# P13_ETH1_RGMII.net
KiCad netlist of a schematic drawn in Altium Designer
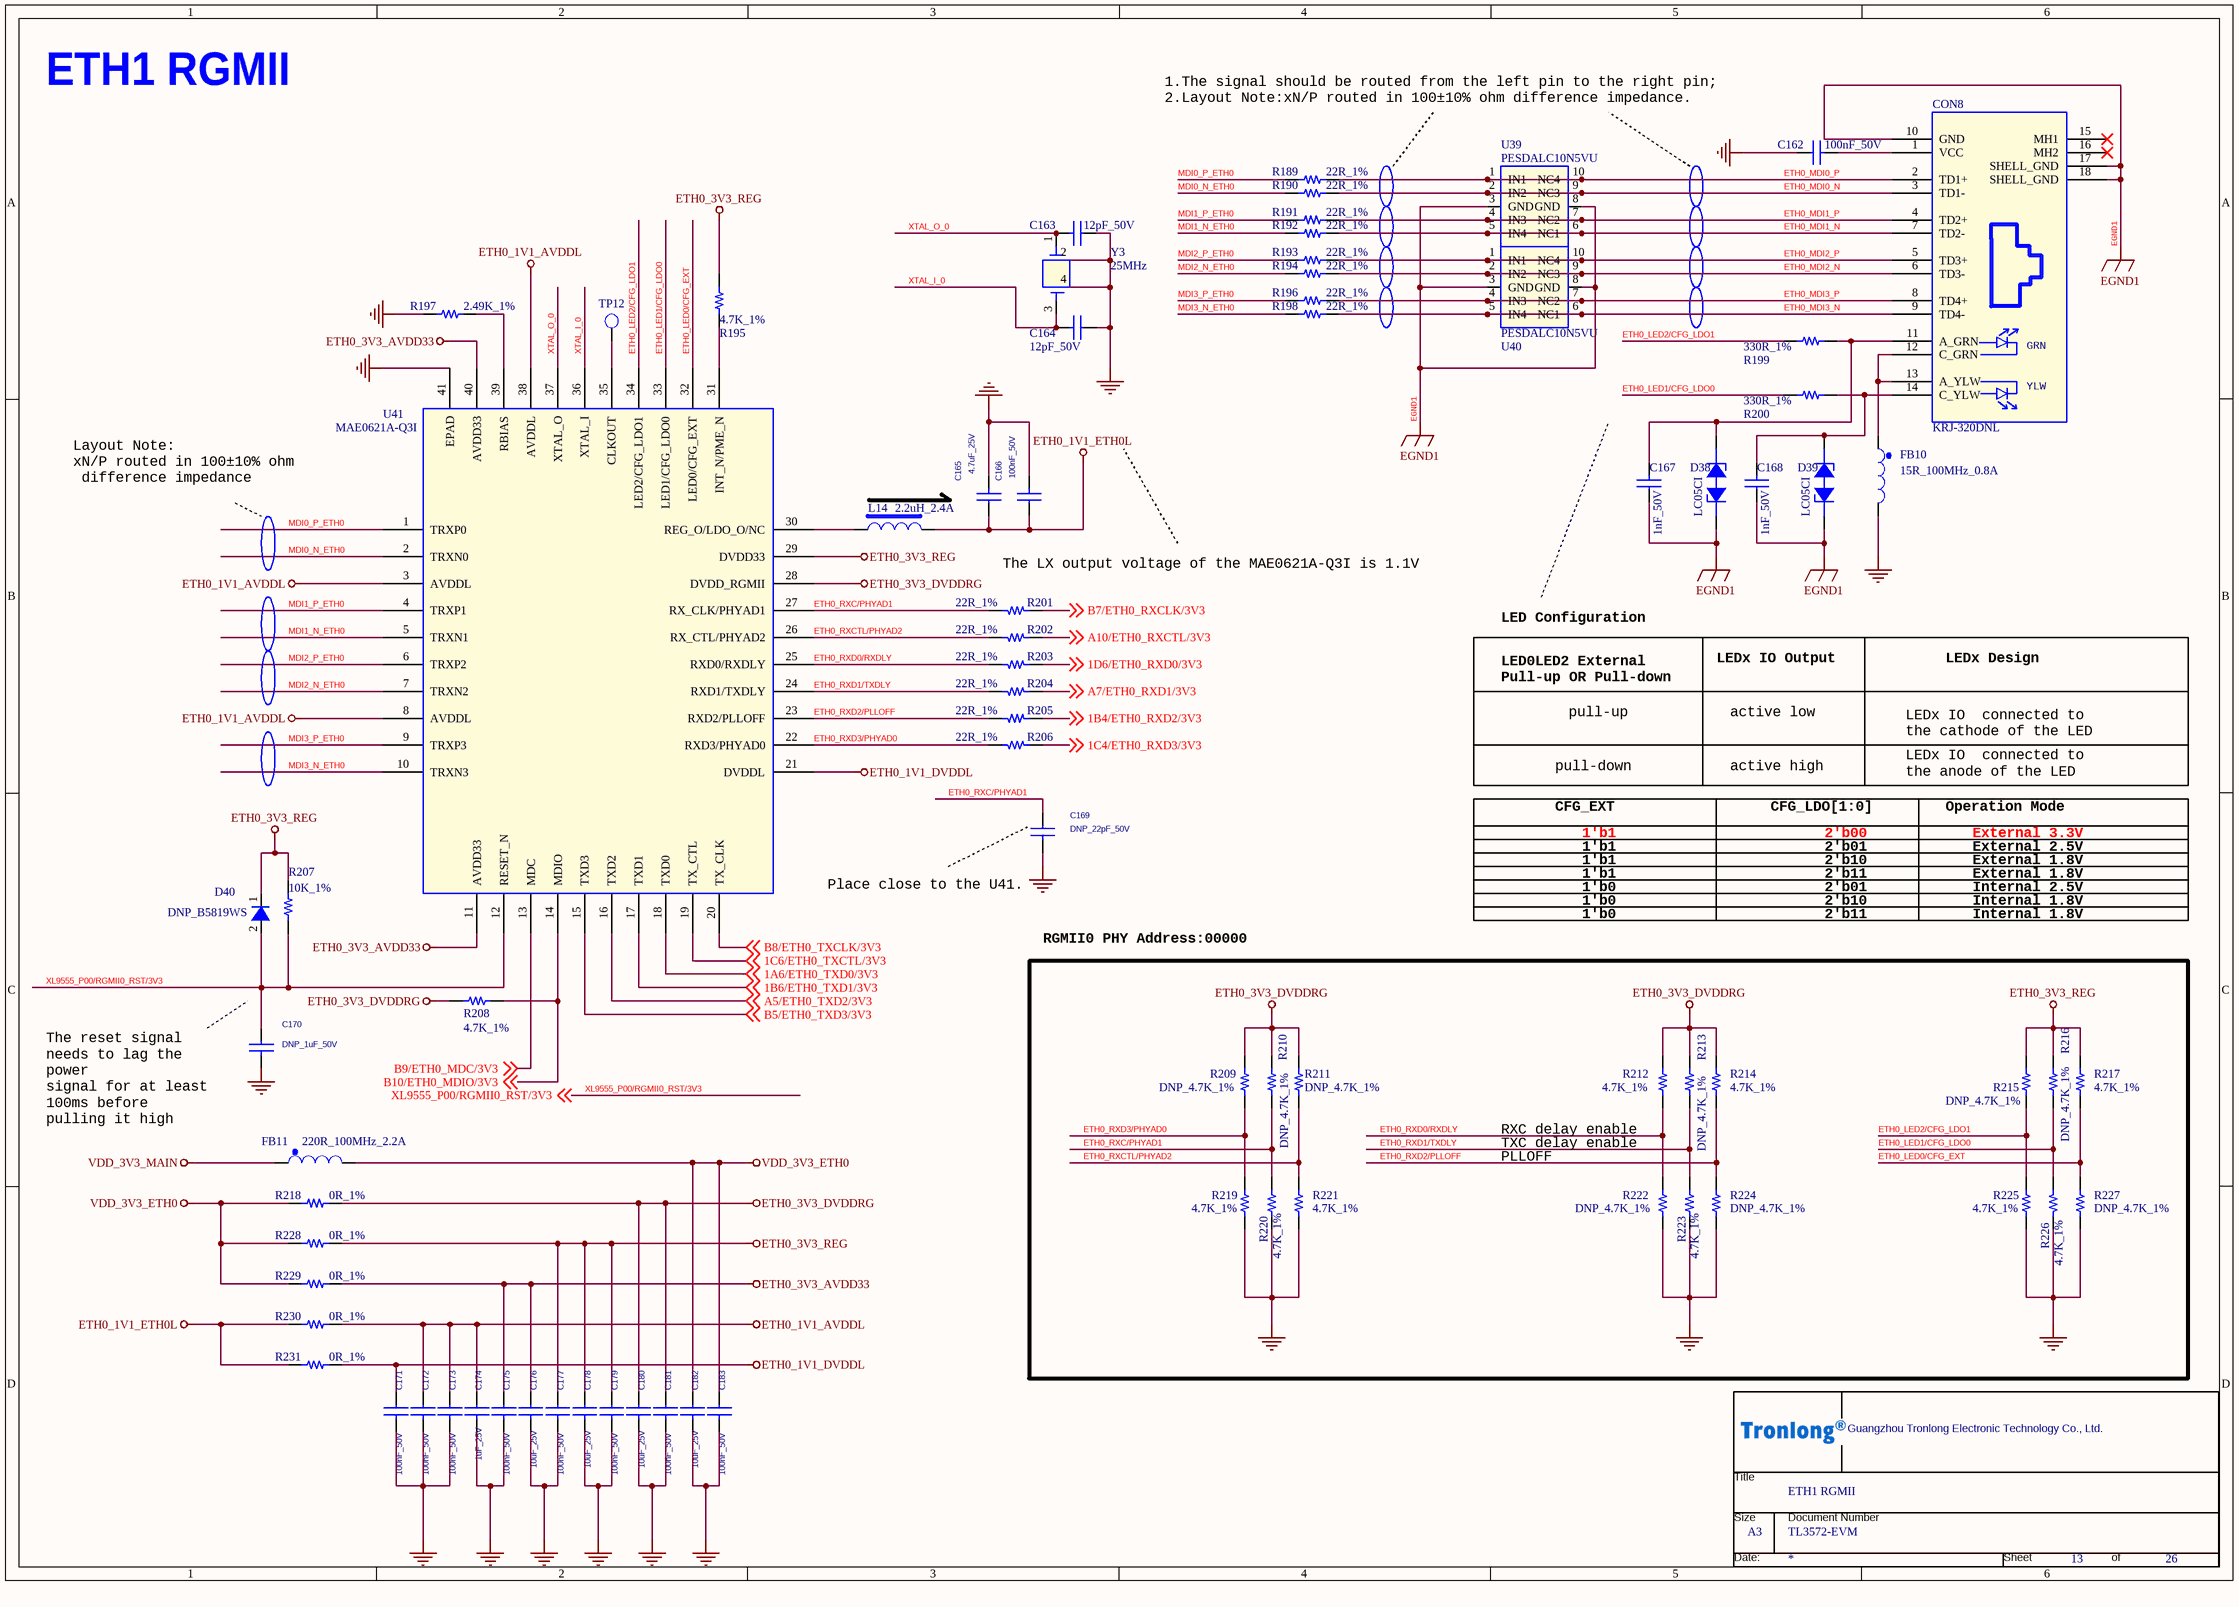
[diagram p0: P13_ETH1 RGMII.SchDoc]

(export (version "E")
  (design (tool "Eeschema 10.0.6"))
  (components
    (comp (ref "C162")
      (value "100nF_50V")
      (footprint "C0402")
      (description "贴片陶瓷电容,100nF,10%,50V,X7R")
      (fields
        (field (name "MANUFACTURER PARTNUMBER") "0402B104K500NT")
        (field (name "MANUFACTURER") "广东风华高新科技股份有限公司（FH）")
      )
      (libsource (lib "*") (part "CAP NP_Dup2"))
    )
    (comp (ref "C163")
      (value "12pF_50V")
      (footprint "C0402")
      (description "贴片陶瓷电容,12pF,5%,50V,COG")
      (fields
        (field (name "MANUFACTURER PARTNUMBER") "0402CG120J500NT")
        (field (name "MANUFACTURER") "广东风华高新科技股份有限公司（FH）")
      )
      (libsource (lib "*") (part "CAP NP_Dup2"))
    )
    (comp (ref "C164")
      (value "12pF_50V")
      (footprint "C0402")
      (description "贴片陶瓷电容,12pF,5%,50V,COG")
      (fields
        (field (name "MANUFACTURER") "广东风华高新科技股份有限公司（FH）")
        (field (name "MANUFACTURER PARTNUMBER") "0402CG120J500NT")
      )
      (libsource (lib "*") (part "CAP NP_Dup2"))
    )
    (comp (ref "C165")
      (value "4.7uF_25V")
      (footprint "C0603")
      (description "贴片陶瓷电容,4.7uF,10%,25V,X5R")
      (fields
        (field (name "MANUFACTURER PARTNUMBER") "0603X475K250NT")
        (field (name "MANUFACTURER") "广东风华高新科技股份有限公司（FH）")
      )
      (libsource (lib "*") (part "CAP NP_Dup2"))
    )
    (comp (ref "C166")
      (value "100nF_50V")
      (footprint "C0402")
      (description "贴片陶瓷电容,100nF,10%,50V,X7R")
      (fields
        (field (name "MANUFACTURER") "广东风华高新科技股份有限公司（FH）")
        (field (name "MANUFACTURER PARTNUMBER") "0402B104K500NT")
      )
      (libsource (lib "*") (part "CAP NP_Dup2"))
    )
    (comp (ref "C167")
      (value "1nF_50V")
      (footprint "C0402")
      (description "贴片陶瓷电容,1nF,10%,50V,X7R")
      (fields
        (field (name "TOLERANCE") "±10%")
        (field (name "MANUFACTURER") "广东风华高新科技股份有限公司（FH）")
        (field (name "CREATED BY") "JJJ")
      )
      (libsource (lib "*") (part "CAP NP_1"))
    )
    (comp (ref "C168")
      (value "1nF_50V")
      (footprint "C0402")
      (description "贴片陶瓷电容,1nF,10%,50V,X7R")
      (fields
        (field (name "TOLERANCE") "±10%")
        (field (name "MANUFACTURER") "广东风华高新科技股份有限公司（FH）")
        (field (name "CREATED BY") "JJJ")
      )
      (libsource (lib "*") (part "CAP NP_1"))
    )
    (comp (ref "C169")
      (value "DNP_22pF_50V")
      (footprint "C0402")
      (description "贴片陶瓷电容,22pF,5%,50V,COG")
      (fields
        (field (name "MANUFACTURER PARTNUMBER") "0402CG220J500NT")
        (field (name "MANUFACTURER") "广东风华高新科技股份有限公司（FH）")
      )
      (libsource (lib "*") (part "CAP NP_Dup2"))
    )
    (comp (ref "C170")
      (value "DNP_1uF_50V")
      (footprint "C0603")
      (description "贴片陶瓷电容,1uF,10%,50V,X5R")
      (fields
        (field (name "MANUFACTURER PARTNUMBER") "0603X105K500NT")
        (field (name "MANUFACTURER") "广东风华高新科技股份有限公司（FH）")
      )
      (libsource (lib "*") (part "CAP NP_Dup2"))
    )
    (comp (ref "C171")
      (value "100nF_50V")
      (footprint "C0402")
      (description "贴片陶瓷电容,100nF,10%,50V,X7R")
      (fields
        (field (name "MANUFACTURER") "广东风华高新科技股份有限公司（FH）")
        (field (name "MANUFACTURER PARTNUMBER") "0402B104K500NT")
      )
      (libsource (lib "*") (part "CAP NP_Dup2"))
    )
    (comp (ref "C172")
      (value "100nF_50V")
      (footprint "C0402")
      (description "贴片陶瓷电容,100nF,10%,50V,X7R")
      (fields
        (field (name "MANUFACTURER") "广东风华高新科技股份有限公司（FH）")
        (field (name "MANUFACTURER PARTNUMBER") "0402B104K500NT")
      )
      (libsource (lib "*") (part "CAP NP_Dup2"))
    )
    (comp (ref "C173")
      (value "100nF_50V")
      (footprint "C0402")
      (description "贴片陶瓷电容,100nF,10%,50V,X7R")
      (fields
        (field (name "MANUFACTURER") "广东风华高新科技股份有限公司（FH）")
        (field (name "MANUFACTURER PARTNUMBER") "0402B104K500NT")
      )
      (libsource (lib "*") (part "CAP NP_Dup2"))
    )
    (comp (ref "C174")
      (value "1uF_25V")
      (footprint "C0402")
      (description "贴片陶瓷电容,1uF,10%,25V,X5R")
      (fields
        (field (name "MANUFACTURER") "广东风华高新科技股份有限公司（FH）")
        (field (name "MANUFACTURER PARTNUMBER") "0402X105K250NT")
      )
      (libsource (lib "*") (part "CAP NP_Dup2"))
    )
    (comp (ref "C175")
      (value "100nF_50V")
      (footprint "C0402")
      (description "贴片陶瓷电容,100nF,10%,50V,X7R")
      (fields
        (field (name "MANUFACTURER") "广东风华高新科技股份有限公司（FH）")
        (field (name "MANUFACTURER PARTNUMBER") "0402B104K500NT")
      )
      (libsource (lib "*") (part "CAP NP_Dup2"))
    )
    (comp (ref "C176")
      (value "10uF_25V")
      (footprint "C0603")
      (description "贴片陶瓷电容,10uF,20%,25V,X5R")
      (fields
        (field (name "MANUFACTURER") "广东风华高新科技股份有限公司（FH）")
        (field (name "MANUFACTURER PARTNUMBER") "0603X106M250NT")
      )
      (libsource (lib "*") (part "CAP NP_Dup2"))
    )
    (comp (ref "C177")
      (value "100nF_50V")
      (footprint "C0402")
      (description "贴片陶瓷电容,100nF,10%,50V,X7R")
      (fields
        (field (name "MANUFACTURER") "广东风华高新科技股份有限公司（FH）")
        (field (name "MANUFACTURER PARTNUMBER") "0402B104K500NT")
      )
      (libsource (lib "*") (part "CAP NP_Dup2"))
    )
    (comp (ref "C178")
      (value "10uF_25V")
      (footprint "C0603")
      (description "贴片陶瓷电容,10uF,20%,25V,X5R")
      (fields
        (field (name "MANUFACTURER PARTNUMBER") "0603X106M250NT")
        (field (name "MANUFACTURER") "广东风华高新科技股份有限公司（FH）")
      )
      (libsource (lib "*") (part "CAP NP_Dup2"))
    )
    (comp (ref "C179")
      (value "100nF_50V")
      (footprint "C0402")
      (description "贴片陶瓷电容,100nF,10%,50V,X7R")
      (fields
        (field (name "MANUFACTURER PARTNUMBER") "0402B104K500NT")
        (field (name "MANUFACTURER") "广东风华高新科技股份有限公司（FH）")
      )
      (libsource (lib "*") (part "CAP NP_Dup2"))
    )
    (comp (ref "C180")
      (value "10uF_25V")
      (footprint "C0603")
      (description "贴片陶瓷电容,10uF,20%,25V,X5R")
      (fields
        (field (name "MANUFACTURER") "广东风华高新科技股份有限公司（FH）")
        (field (name "MANUFACTURER PARTNUMBER") "0603X106M250NT")
      )
      (libsource (lib "*") (part "CAP NP_Dup2"))
    )
    (comp (ref "C181")
      (value "100nF_50V")
      (footprint "C0402")
      (description "贴片陶瓷电容,100nF,10%,50V,X7R")
      (fields
        (field (name "MANUFACTURER") "广东风华高新科技股份有限公司（FH）")
        (field (name "MANUFACTURER PARTNUMBER") "0402B104K500NT")
      )
      (libsource (lib "*") (part "CAP NP_Dup2"))
    )
    (comp (ref "C182")
      (value "10uF_25V")
      (footprint "C0603")
      (description "贴片陶瓷电容,10uF,20%,25V,X5R")
      (fields
        (field (name "MANUFACTURER") "广东风华高新科技股份有限公司（FH）")
        (field (name "MANUFACTURER PARTNUMBER") "0603X106M250NT")
      )
      (libsource (lib "*") (part "CAP NP_Dup2"))
    )
    (comp (ref "C183")
      (value "100nF_50V")
      (footprint "C0402")
      (description "贴片陶瓷电容,100nF,10%,50V,X7R")
      (fields
        (field (name "MANUFACTURER") "广东风华高新科技股份有限公司（FH）")
        (field (name "MANUFACTURER PARTNUMBER") "0402B104K500NT")
      )
      (libsource (lib "*") (part "CAP NP_Dup2"))
    )
    (comp (ref "CON8")
      (value "KRJ-320DNL")
      (footprint "KRJ-320DNL_14P")
      (description "RJ45连接器,14P,2.54mm间距,单层母座,90度,插件")
      (fields (field (name "MANUFACTURER") "东莞市科优达电子科技有限公司（DGKYD）"))
      (libsource (lib "*") (part "KRJ-320DNL_0"))
    )
    (comp (ref "D38")
      (value "LC05CI")
      (footprint "SOD323")
      (description "TVS二极管,VRWM=5V,VBR=6V,一组,双向,30KV,30KV")
      (fields
        (field (name "MANUFACTURER PART NUMBER") "PESD3V3L1BA")
        (field (name "MANUFACTURER") "上海雷卯电子科技有限公司（Leiditech）")
      )
      (libsource (lib "*") (part "DIODE BREAKDOWN_2"))
    )
    (comp (ref "D39")
      (value "LC05CI")
      (footprint "SOD323")
      (description "TVS二极管,VRWM=5V,VBR=6V,一组,双向,30KV,30KV")
      (fields
        (field (name "MANUFACTURER") "上海雷卯电子科技有限公司（Leiditech）")
        (field (name "MANUFACTURER PART NUMBER") "PESD3V3L1BA")
      )
      (libsource (lib "*") (part "DIODE BREAKDOWN_2"))
    )
    (comp (ref "D40")
      (value "DNP_B5819WS")
      (footprint "SOD-323")
      (description "肖特基二极管,VR=40V,IF=1A,VF=0.6V@1A")
      (fields (field (name "TIINTPARTNUMBER") "1E0013") (field (name "MFR") "On Semiconductor"))
      (libsource (lib "*") (part "Diode200mA250V"))
    )
    (comp (ref "FB10")
      (value "15R_100MHz_0.8A")
      (footprint "L0603")
      (description "磁珠,100mΩ,0.8A,15R@100MHz")
      (fields
        (field (name "MANUFACTURER PARTNUMBER") "CBG160808U150T")
        (field (name "MANUFACTURER") "广东风华高新科技股份有限公司(FH)")
      )
      (libsource (lib "*") (part "FB_0"))
    )
    (comp (ref "FB11")
      (value "220R_100MHz_2.2A")
      (footprint "L0603")
      (description "磁珠,50mΩ,2.2A,220R@100MHz")
      (fields
        (field (name "MANUFACTURER PARTNUMBER") "UPZ1608U221-2R2TF")
        (field (name "MANUFACTURER") "深圳顺络电子股份有限公司（Sunlord）")
      )
      (libsource (lib "*") (part "FERRITE BEAD_Dup1"))
    )
    (comp (ref "L14")
      (value "2.2uH_2.4A")
      (footprint "SMD-L2520M-2P")
      (description "贴片功率电感,2.2uH,0.096Ω,Isat=2.9A,Irms=2.4A")
      (fields
        (field (name "MANUFACTURER") "深圳顺络电子股份有限公司(Sunlord)")
        (field (name "MANUFACTURER PARTNUMBER") "WPN252010U2R2MT")
      )
      (libsource (lib "*") (part "INDUCTOR"))
    )
    (comp (ref "R189")
      (value "22R_1%")
      (footprint "R0402")
      (description "贴片电阻,22R,±1%,1/16W")
      (fields
        (field (name "MANUFACTURER PARTNUMBER") "RC-02K22R0FT")
        (field (name "TOLERANCE") "5%")
        (field (name "CREATED BY") "YTL")
      )
      (libsource (lib "*") (part "Resistor_Dup1"))
    )
    (comp (ref "R190")
      (value "22R_1%")
      (footprint "R0402")
      (description "贴片电阻,22R,±1%,1/16W")
      (fields
        (field (name "MANUFACTURER PARTNUMBER") "RC-02K22R0FT")
        (field (name "TOLERANCE") "5%")
        (field (name "CREATED BY") "YTL")
      )
      (libsource (lib "*") (part "Resistor_Dup1"))
    )
    (comp (ref "R191")
      (value "22R_1%")
      (footprint "R0402")
      (description "贴片电阻,22R,±1%,1/16W")
      (fields
        (field (name "MANUFACTURER PARTNUMBER") "RC-02K22R0FT")
        (field (name "TOLERANCE") "5%")
        (field (name "CREATED BY") "YTL")
      )
      (libsource (lib "*") (part "Resistor_Dup1"))
    )
    (comp (ref "R192")
      (value "22R_1%")
      (footprint "R0402")
      (description "贴片电阻,22R,±1%,1/16W")
      (fields
        (field (name "MANUFACTURER PARTNUMBER") "RC-02K22R0FT")
        (field (name "TOLERANCE") "5%")
        (field (name "CREATED BY") "YTL")
      )
      (libsource (lib "*") (part "Resistor_Dup1"))
    )
    (comp (ref "R193")
      (value "22R_1%")
      (footprint "R0402")
      (description "贴片电阻,22R,±1%,1/16W")
      (fields
        (field (name "MANUFACTURER PARTNUMBER") "RC-02K22R0FT")
        (field (name "TOLERANCE") "5%")
        (field (name "CREATED BY") "YTL")
      )
      (libsource (lib "*") (part "Resistor_Dup1"))
    )
    (comp (ref "R194")
      (value "22R_1%")
      (footprint "R0402")
      (description "贴片电阻,22R,±1%,1/16W")
      (fields
        (field (name "MANUFACTURER PARTNUMBER") "RC-02K22R0FT")
        (field (name "TOLERANCE") "5%")
        (field (name "CREATED BY") "YTL")
      )
      (libsource (lib "*") (part "Resistor_Dup1"))
    )
    (comp (ref "R195")
      (value "4.7K_1%")
      (footprint "R0402")
      (description "贴片电阻,4.7K,±1%,1/16W")
      (fields
        (field (name "MANUFACTURER") "广东风华高新科技股份有限公司（FH）")
        (field (name "MANUFACTURER PARTNUMBER") "RC-02K4701FT")
      )
      (libsource (lib "*") (part "Resistor_Dup3"))
    )
    (comp (ref "R196")
      (value "22R_1%")
      (footprint "R0402")
      (description "贴片电阻,22R,±1%,1/16W")
      (fields
        (field (name "MANUFACTURER PARTNUMBER") "RC-02K22R0FT")
        (field (name "TOLERANCE") "5%")
        (field (name "CREATED BY") "YTL")
      )
      (libsource (lib "*") (part "Resistor_Dup1"))
    )
    (comp (ref "R197")
      (value "2.49K_1%")
      (footprint "R0603")
      (description "贴片电阻,2.49K,±1%,1/10W")
      (fields
        (field (name "MANUFACTURER") "广东风华高新科技股份有限公司（FH）")
        (field (name "MANUFACTURER PARTNUMBER") "RS-03K2491FT")
      )
      (libsource (lib "*") (part "Resistor_Dup3"))
    )
    (comp (ref "R198")
      (value "22R_1%")
      (footprint "R0402")
      (description "贴片电阻,22R,±1%,1/16W")
      (fields
        (field (name "MANUFACTURER PARTNUMBER") "RC-02K22R0FT")
        (field (name "TOLERANCE") "5%")
        (field (name "CREATED BY") "YTL")
      )
      (libsource (lib "*") (part "Resistor_Dup1"))
    )
    (comp (ref "R199")
      (value "330R_1%")
      (footprint "R0402")
      (description "RC0402FR-07330RL,0402WGF3300TCE")
      (fields
        (field (name "MANUFACTURER") "广州创龙")
        (field (name "MANUFACTURER PARTNUMBER") "330R,±1%,R0402,≥1/16W")
      )
      (libsource (lib "*") (part "Resistor_Dup3"))
    )
    (comp (ref "R200")
      (value "330R_1%")
      (footprint "R0402")
      (description "RC0402FR-07330RL,0402WGF3300TCE")
      (fields
        (field (name "MANUFACTURER") "广州创龙")
        (field (name "MANUFACTURER PARTNUMBER") "330R,±1%,R0402,≥1/16W")
      )
      (libsource (lib "*") (part "Resistor_Dup3"))
    )
    (comp (ref "R201")
      (value "22R_1%")
      (footprint "R0402")
      (description "贴片电阻,22R,±1%,1/16W")
      (fields
        (field (name "MANUFACTURER PARTNUMBER") "RC-02K22R0FT")
        (field (name "MANUFACTURER") "广东风华高新科技股份有限公司（FH）")
      )
      (libsource (lib "*") (part "Resistor_Dup3"))
    )
    (comp (ref "R202")
      (value "22R_1%")
      (footprint "R0402")
      (description "贴片电阻,22R,±1%,1/16W")
      (fields
        (field (name "MANUFACTURER") "广东风华高新科技股份有限公司（FH）")
        (field (name "MANUFACTURER PARTNUMBER") "RC-02K22R0FT")
      )
      (libsource (lib "*") (part "Resistor_Dup3"))
    )
    (comp (ref "R203")
      (value "22R_1%")
      (footprint "R0402")
      (description "贴片电阻,22R,±1%,1/16W")
      (fields
        (field (name "MANUFACTURER") "广东风华高新科技股份有限公司（FH）")
        (field (name "MANUFACTURER PARTNUMBER") "RC-02K22R0FT")
      )
      (libsource (lib "*") (part "Resistor_Dup3"))
    )
    (comp (ref "R204")
      (value "22R_1%")
      (footprint "R0402")
      (description "贴片电阻,22R,±1%,1/16W")
      (fields
        (field (name "MANUFACTURER PARTNUMBER") "RC-02K22R0FT")
        (field (name "MANUFACTURER") "广东风华高新科技股份有限公司（FH）")
      )
      (libsource (lib "*") (part "Resistor_Dup3"))
    )
    (comp (ref "R205")
      (value "22R_1%")
      (footprint "R0402")
      (description "贴片电阻,22R,±1%,1/16W")
      (fields
        (field (name "MANUFACTURER") "广东风华高新科技股份有限公司（FH）")
        (field (name "MANUFACTURER PARTNUMBER") "RC-02K22R0FT")
      )
      (libsource (lib "*") (part "Resistor_Dup3"))
    )
    (comp (ref "R206")
      (value "22R_1%")
      (footprint "R0402")
      (description "贴片电阻,22R,±1%,1/16W")
      (fields
        (field (name "MANUFACTURER") "广东风华高新科技股份有限公司（FH）")
        (field (name "MANUFACTURER PARTNUMBER") "RC-02K22R0FT")
      )
      (libsource (lib "*") (part "Resistor_Dup3"))
    )
    (comp (ref "R207")
      (value "10K_1%")
      (footprint "R0402")
      (description "贴片电阻,10K,±1%,1/16W")
      (fields
        (field (name "MANUFACTURER") "广东风华高新科技股份有限公司（FH）")
        (field (name "MANUFACTURER PARTNUMBER") "RC-02K1002FT")
      )
      (libsource (lib "*") (part "Resistor_Dup3"))
    )
    (comp (ref "R208")
      (value "4.7K_1%")
      (footprint "R0402")
      (description "贴片电阻,4.7K,±1%,1/16W")
      (fields
        (field (name "MANUFACTURER PARTNUMBER") "RC-02K4701FT")
        (field (name "MANUFACTURER") "广东风华高新科技股份有限公司（FH）")
      )
      (libsource (lib "*") (part "Resistor_Dup3"))
    )
    (comp (ref "R209")
      (value "DNP_4.7K_1%")
      (footprint "R0402")
      (description "RC0402FR-074K7L,0402WGF4701TCE")
      (fields
        (field (name "MANUFACTURER PARTNUMBER") "4.7K,±1%,R0402,≥1/16W")
        (field (name "MANUFACTURER") "广州创龙")
      )
      (libsource (lib "*") (part "Resistor_Dup3"))
    )
    (comp (ref "R210")
      (value "DNP_4.7K_1%")
      (footprint "R0402")
      (description "RC0402FR-074K7L,0402WGF4701TCE")
      (fields
        (field (name "MANUFACTURER") "广州创龙")
        (field (name "MANUFACTURER PARTNUMBER") "4.7K,±1%,R0402,≥1/16W")
      )
      (libsource (lib "*") (part "Resistor_Dup3"))
    )
    (comp (ref "R211")
      (value "DNP_4.7K_1%")
      (footprint "R0402")
      (description "RC0402FR-074K7L,0402WGF4701TCE")
      (fields
        (field (name "MANUFACTURER PARTNUMBER") "4.7K,±1%,R0402,≥1/16W")
        (field (name "MANUFACTURER") "广州创龙")
      )
      (libsource (lib "*") (part "Resistor_Dup3"))
    )
    (comp (ref "R212")
      (value "4.7K_1%")
      (footprint "R0402")
      (description "贴片电阻,4.7K,±1%,1/16W")
      (fields
        (field (name "MANUFACTURER") "广东风华高新科技股份有限公司（FH）")
        (field (name "MANUFACTURER PARTNUMBER") "RC-02K4701FT")
      )
      (libsource (lib "*") (part "Resistor_Dup3"))
    )
    (comp (ref "R213")
      (value "DNP_4.7K_1%")
      (footprint "R0402")
      (description "RC0402FR-074K7L,0402WGF4701TCE")
      (fields
        (field (name "MANUFACTURER") "广州创龙")
        (field (name "MANUFACTURER PARTNUMBER") "4.7K,±1%,R0402,≥1/16W")
      )
      (libsource (lib "*") (part "Resistor_Dup3"))
    )
    (comp (ref "R214")
      (value "4.7K_1%")
      (footprint "R0402")
      (description "贴片电阻,4.7K,±1%,1/16W")
      (fields
        (field (name "MANUFACTURER PARTNUMBER") "RC-02K4701FT")
        (field (name "MANUFACTURER") "广东风华高新科技股份有限公司（FH）")
      )
      (libsource (lib "*") (part "Resistor_Dup3"))
    )
    (comp (ref "R215")
      (value "DNP_4.7K_1%")
      (footprint "R0402")
      (description "RC0402FR-074K7L,0402WGF4701TCE")
      (fields
        (field (name "MANUFACTURER") "广州创龙")
        (field (name "MANUFACTURER PARTNUMBER") "4.7K,±1%,R0402,≥1/16W")
      )
      (libsource (lib "*") (part "Resistor_Dup3"))
    )
    (comp (ref "R216")
      (value "DNP_4.7K_1%")
      (footprint "R0402")
      (description "RC0402FR-074K7L,0402WGF4701TCE")
      (fields
        (field (name "MANUFACTURER PARTNUMBER") "4.7K,±1%,R0402,≥1/16W")
        (field (name "MANUFACTURER") "广州创龙")
      )
      (libsource (lib "*") (part "Resistor_Dup3"))
    )
    (comp (ref "R217")
      (value "4.7K_1%")
      (footprint "R0402")
      (description "贴片电阻,4.7K,±1%,1/16W")
      (fields
        (field (name "MANUFACTURER PARTNUMBER") "RC-02K4701FT")
        (field (name "MANUFACTURER") "广东风华高新科技股份有限公司（FH）")
      )
      (libsource (lib "*") (part "Resistor_Dup3"))
    )
    (comp (ref "R218")
      (value "0R_1%")
      (footprint "R0603")
      (description "贴片电阻,0R,±1%,1/10W")
      (fields
        (field (name "MANUFACTURER PARTNUMBER") "RS-03000FT")
        (field (name "MANUFACTURER") "广东风华高新科技股份有限公司（FH）")
      )
      (libsource (lib "*") (part "Resistor_Dup3"))
    )
    (comp (ref "R219")
      (value "4.7K_1%")
      (footprint "R0402")
      (description "贴片电阻,4.7K,±1%,1/16W")
      (fields
        (field (name "MANUFACTURER") "广东风华高新科技股份有限公司（FH）")
        (field (name "MANUFACTURER PARTNUMBER") "RC-02K4701FT")
      )
      (libsource (lib "*") (part "Resistor_Dup3"))
    )
    (comp (ref "R220")
      (value "4.7K_1%")
      (footprint "R0402")
      (description "贴片电阻,4.7K,±1%,1/16W")
      (fields
        (field (name "MANUFACTURER") "广东风华高新科技股份有限公司（FH）")
        (field (name "MANUFACTURER PARTNUMBER") "RC-02K4701FT")
      )
      (libsource (lib "*") (part "Resistor_Dup3"))
    )
    (comp (ref "R221")
      (value "4.7K_1%")
      (footprint "R0402")
      (description "贴片电阻,4.7K,±1%,1/16W")
      (fields
        (field (name "MANUFACTURER") "广东风华高新科技股份有限公司（FH）")
        (field (name "MANUFACTURER PARTNUMBER") "RC-02K4701FT")
      )
      (libsource (lib "*") (part "Resistor_Dup3"))
    )
    (comp (ref "R222")
      (value "DNP_4.7K_1%")
      (footprint "R0402")
      (description "RC0402FR-074K7L,0402WGF4701TCE")
      (fields
        (field (name "MANUFACTURER PARTNUMBER") "4.7K,±1%,R0402,≥1/16W")
        (field (name "MANUFACTURER") "广州创龙")
      )
      (libsource (lib "*") (part "Resistor_Dup3"))
    )
    (comp (ref "R223")
      (value "4.7K_1%")
      (footprint "R0402")
      (description "贴片电阻,4.7K,±1%,1/16W")
      (fields
        (field (name "MANUFACTURER") "广东风华高新科技股份有限公司（FH）")
        (field (name "MANUFACTURER PARTNUMBER") "RC-02K4701FT")
      )
      (libsource (lib "*") (part "Resistor_Dup3"))
    )
    (comp (ref "R224")
      (value "DNP_4.7K_1%")
      (footprint "R0402")
      (description "RC0402FR-074K7L,0402WGF4701TCE")
      (fields
        (field (name "MANUFACTURER PARTNUMBER") "4.7K,±1%,R0402,≥1/16W")
        (field (name "MANUFACTURER") "广州创龙")
      )
      (libsource (lib "*") (part "Resistor_Dup3"))
    )
    (comp (ref "R225")
      (value "4.7K_1%")
      (footprint "R0402")
      (description "贴片电阻,4.7K,±1%,1/16W")
      (fields
        (field (name "MANUFACTURER PARTNUMBER") "RC-02K4701FT")
        (field (name "MANUFACTURER") "广东风华高新科技股份有限公司（FH）")
      )
      (libsource (lib "*") (part "Resistor_Dup3"))
    )
    (comp (ref "R226")
      (value "4.7K_1%")
      (footprint "R0402")
      (description "贴片电阻,4.7K,±1%,1/16W")
      (fields
        (field (name "MANUFACTURER PARTNUMBER") "RC-02K4701FT")
        (field (name "MANUFACTURER") "广东风华高新科技股份有限公司（FH）")
      )
      (libsource (lib "*") (part "Resistor_Dup3"))
    )
    (comp (ref "R227")
      (value "DNP_4.7K_1%")
      (footprint "R0402")
      (description "RC0402FR-074K7L,0402WGF4701TCE")
      (fields
        (field (name "MANUFACTURER") "广州创龙")
        (field (name "MANUFACTURER PARTNUMBER") "4.7K,±1%,R0402,≥1/16W")
      )
      (libsource (lib "*") (part "Resistor_Dup3"))
    )
    (comp (ref "R228")
      (value "0R_1%")
      (footprint "R0603")
      (description "贴片电阻,0R,±1%,1/10W")
      (fields
        (field (name "MANUFACTURER PARTNUMBER") "RS-03000FT")
        (field (name "MANUFACTURER") "广东风华高新科技股份有限公司（FH）")
      )
      (libsource (lib "*") (part "Resistor_Dup3"))
    )
    (comp (ref "R229")
      (value "0R_1%")
      (footprint "R0603")
      (description "贴片电阻,0R,±1%,1/10W")
      (fields
        (field (name "MANUFACTURER PARTNUMBER") "RS-03000FT")
        (field (name "MANUFACTURER") "广东风华高新科技股份有限公司（FH）")
      )
      (libsource (lib "*") (part "Resistor_Dup3"))
    )
    (comp (ref "R230")
      (value "0R_1%")
      (footprint "R0603")
      (description "贴片电阻,0R,±1%,1/10W")
      (fields
        (field (name "MANUFACTURER") "广东风华高新科技股份有限公司（FH）")
        (field (name "MANUFACTURER PARTNUMBER") "RS-03000FT")
      )
      (libsource (lib "*") (part "Resistor_Dup3"))
    )
    (comp (ref "R231")
      (value "0R_1%")
      (footprint "R0603")
      (description "贴片电阻,0R,±1%,1/10W")
      (fields
        (field (name "MANUFACTURER PARTNUMBER") "RS-03000FT")
        (field (name "MANUFACTURER") "广东风华高新科技股份有限公司（FH）")
      )
      (libsource (lib "*") (part "Resistor_Dup3"))
    )
    (comp (ref "TP12")
      (value "SMT TP")
      (footprint "TP30")
      (description "/")
      (libsource (lib "*") (part "T POINT R"))
    )
    (comp (ref "U39")
      (value "PESDALC10N5VU")
      (footprint "DFN-10-2510")
      (description "ESD二极管,VRWM=5V,VBR=6V,四组,单向,15KV,30KV")
      (fields (field (name "MANUFACTURER") "上海芯导电子科技股份有限公司（Prisemi）"))
      (libsource (lib "*") (part "SU099PGTR"))
    )
    (comp (ref "U40")
      (value "PESDALC10N5VU")
      (footprint "DFN-10-2510")
      (description "ESD二极管,VRWM=5V,VBR=6V,四组,单向,15KV,30KV")
      (fields (field (name "MANUFACTURER") "上海芯导电子科技股份有限公司（Prisemi）"))
      (libsource (lib "*") (part "SU099PGTR"))
    )
    (comp (ref "U41")
      (value "MAE0621A-Q3I")
      (footprint "QFN40_5x5")
      (description "以太网收发器，RGMII/GMII/MII")
      (fields (field (name "MANUFACTURER") "联芸科技（杭州）股份有限公司"))
      (libsource (lib "*") (part "YT8531H-CA"))
    )
    (comp (ref "Y3")
      (value "25MHz")
      (footprint "SMD_3225")
      (description "四脚无源晶振,25MHz,±10ppm,12pF,30Ω,±30ppm")
      (fields
        (field (name "MANUFACTURER PARTNUMBER") "S3B25.000F1210F30")
        (field (name "MANUFACTURER") "深圳市星通时频电子有限公司（SCTF）")
      )
      (libsource (lib "*") (part "CRYSTAL-4 PIN"))
    )
  )
  (nets
    (net (code "1") (name "/ETH0_LED0{slash}CFG_EXT") (class "Default")
      (node (ref "R217") (pin "1") (pinfunction "1_1") (pintype "passive"))
      (node (ref "R227") (pin "2") (pinfunction "2_2") (pintype "passive"))
      (node (ref "U41") (pin "32") (pinfunction "LED0/CFG_EXT_32") (pintype "passive"))
    )
    (net (code "2") (name "/ETH0_LED1{slash}CFG_LDO0") (class "Default")
      (node (ref "R200") (pin "1") (pinfunction "1_1") (pintype "passive"))
      (node (ref "R216") (pin "1") (pinfunction "1_1") (pintype "passive"))
      (node (ref "R226") (pin "2") (pinfunction "2_2") (pintype "passive"))
      (node (ref "U41") (pin "33") (pinfunction "LED1/CFG_LDO0_33") (pintype "passive"))
    )
    (net (code "3") (name "/ETH0_LED2{slash}CFG_LDO1") (class "Default")
      (node (ref "R199") (pin "1") (pinfunction "1_1") (pintype "passive"))
      (node (ref "R215") (pin "1") (pinfunction "1_1") (pintype "passive"))
      (node (ref "R225") (pin "2") (pinfunction "2_2") (pintype "passive"))
      (node (ref "U41") (pin "34") (pinfunction "LED2/CFG_LDO1_34") (pintype "passive"))
    )
    (net (code "4") (name "/ETH0_MDI0_N") (class "Default")
      (node (ref "CON8") (pin "3") (pinfunction "TD1-_3") (pintype "passive"))
      (node (ref "R190") (pin "2") (pinfunction "2_2") (pintype "passive"))
      (node (ref "U39") (pin "2") (pinfunction "IN2_2") (pintype "passive"))
      (node (ref "U39") (pin "9") (pinfunction "NC3_9") (pintype "passive"))
    )
    (net (code "5") (name "/ETH0_MDI0_P") (class "Default")
      (node (ref "CON8") (pin "2") (pinfunction "TD1+_2") (pintype "passive"))
      (node (ref "R189") (pin "2") (pinfunction "2_2") (pintype "passive"))
      (node (ref "U39") (pin "1") (pinfunction "IN1_1") (pintype "passive"))
      (node (ref "U39") (pin "10") (pinfunction "NC4_10") (pintype "passive"))
    )
    (net (code "6") (name "/ETH0_MDI1_N") (class "Default")
      (node (ref "CON8") (pin "7") (pinfunction "TD2-_7") (pintype "passive"))
      (node (ref "R192") (pin "2") (pinfunction "2_2") (pintype "passive"))
      (node (ref "U39") (pin "5") (pinfunction "IN4_5") (pintype "passive"))
      (node (ref "U39") (pin "6") (pinfunction "NC1_6") (pintype "passive"))
    )
    (net (code "7") (name "/ETH0_MDI1_P") (class "Default")
      (node (ref "CON8") (pin "4") (pinfunction "TD2+_4") (pintype "passive"))
      (node (ref "R191") (pin "2") (pinfunction "2_2") (pintype "passive"))
      (node (ref "U39") (pin "4") (pinfunction "IN3_4") (pintype "passive"))
      (node (ref "U39") (pin "7") (pinfunction "NC2_7") (pintype "passive"))
    )
    (net (code "8") (name "/ETH0_MDI2_N") (class "Default")
      (node (ref "CON8") (pin "6") (pinfunction "TD3-_6") (pintype "passive"))
      (node (ref "R194") (pin "2") (pinfunction "2_2") (pintype "passive"))
      (node (ref "U40") (pin "2") (pinfunction "IN2_2") (pintype "passive"))
      (node (ref "U40") (pin "9") (pinfunction "NC3_9") (pintype "passive"))
    )
    (net (code "9") (name "/ETH0_MDI2_P") (class "Default")
      (node (ref "CON8") (pin "5") (pinfunction "TD3+_5") (pintype "passive"))
      (node (ref "R193") (pin "2") (pinfunction "2_2") (pintype "passive"))
      (node (ref "U40") (pin "1") (pinfunction "IN1_1") (pintype "passive"))
      (node (ref "U40") (pin "10") (pinfunction "NC4_10") (pintype "passive"))
    )
    (net (code "10") (name "/ETH0_MDI3_N") (class "Default")
      (node (ref "CON8") (pin "9") (pinfunction "TD4-_9") (pintype "passive"))
      (node (ref "R198") (pin "2") (pinfunction "2_2") (pintype "passive"))
      (node (ref "U40") (pin "5") (pinfunction "IN4_5") (pintype "passive"))
      (node (ref "U40") (pin "6") (pinfunction "NC1_6") (pintype "passive"))
    )
    (net (code "11") (name "/ETH0_MDI3_P") (class "Default")
      (node (ref "CON8") (pin "8") (pinfunction "TD4+_8") (pintype "passive"))
      (node (ref "R196") (pin "2") (pinfunction "2_2") (pintype "passive"))
      (node (ref "U40") (pin "4") (pinfunction "IN3_4") (pintype "passive"))
      (node (ref "U40") (pin "7") (pinfunction "NC2_7") (pintype "passive"))
    )
    (net (code "12") (name "/ETH0_RXCTL{slash}PHYAD2") (class "Default")
      (node (ref "R202") (pin "2") (pinfunction "2_2") (pintype "passive"))
      (node (ref "R211") (pin "1") (pinfunction "1_1") (pintype "passive"))
      (node (ref "R221") (pin "2") (pinfunction "2_2") (pintype "passive"))
      (node (ref "U41") (pin "26") (pinfunction "RX_CTL/PHYAD2_26") (pintype "passive"))
    )
    (net (code "13") (name "/ETH0_RXC{slash}PHYAD1") (class "Default")
      (node (ref "C169") (pin "1") (pinfunction "1_1") (pintype "passive"))
      (node (ref "R201") (pin "2") (pinfunction "2_2") (pintype "passive"))
      (node (ref "R210") (pin "1") (pinfunction "1_1") (pintype "passive"))
      (node (ref "R220") (pin "2") (pinfunction "2_2") (pintype "passive"))
      (node (ref "U41") (pin "27") (pinfunction "RX_CLK/PHYAD1_27") (pintype "passive"))
    )
    (net (code "14") (name "/ETH0_RXD0{slash}RXDLY") (class "Default")
      (node (ref "R203") (pin "2") (pinfunction "2_2") (pintype "passive"))
      (node (ref "R212") (pin "1") (pinfunction "1_1") (pintype "passive"))
      (node (ref "R222") (pin "2") (pinfunction "2_2") (pintype "passive"))
      (node (ref "U41") (pin "25") (pinfunction "RXD0/RXDLY_25") (pintype "passive"))
    )
    (net (code "15") (name "/ETH0_RXD1{slash}TXDLY") (class "Default")
      (node (ref "R204") (pin "2") (pinfunction "2_2") (pintype "passive"))
      (node (ref "R213") (pin "1") (pinfunction "1_1") (pintype "passive"))
      (node (ref "R223") (pin "2") (pinfunction "2_2") (pintype "passive"))
      (node (ref "U41") (pin "24") (pinfunction "RXD1/TXDLY_24") (pintype "passive"))
    )
    (net (code "16") (name "/ETH0_RXD2{slash}PLLOFF") (class "Default")
      (node (ref "R205") (pin "2") (pinfunction "2_2") (pintype "passive"))
      (node (ref "R214") (pin "1") (pinfunction "1_1") (pintype "passive"))
      (node (ref "R224") (pin "2") (pinfunction "2_2") (pintype "passive"))
      (node (ref "U41") (pin "23") (pinfunction "RXD2/PLLOFF_23") (pintype "passive"))
    )
    (net (code "17") (name "/ETH0_RXD3{slash}PHYAD0") (class "Default")
      (node (ref "R206") (pin "2") (pinfunction "2_2") (pintype "passive"))
      (node (ref "R209") (pin "1") (pinfunction "1_1") (pintype "passive"))
      (node (ref "R219") (pin "2") (pinfunction "2_2") (pintype "passive"))
      (node (ref "U41") (pin "22") (pinfunction "RXD3/PHYAD0_22") (pintype "passive"))
    )
    (net (code "18") (name "/MDI0_N_ETH0") (class "Default")
      (node (ref "R190") (pin "1") (pinfunction "1_1") (pintype "passive"))
      (node (ref "U41") (pin "2") (pinfunction "TRXN0_2") (pintype "passive"))
    )
    (net (code "19") (name "/MDI0_P_ETH0") (class "Default")
      (node (ref "R189") (pin "1") (pinfunction "1_1") (pintype "passive"))
      (node (ref "U41") (pin "1") (pinfunction "TRXP0_1") (pintype "passive"))
    )
    (net (code "20") (name "/MDI1_N_ETH0") (class "Default")
      (node (ref "R192") (pin "1") (pinfunction "1_1") (pintype "passive"))
      (node (ref "U41") (pin "5") (pinfunction "TRXN1_5") (pintype "passive"))
    )
    (net (code "21") (name "/MDI1_P_ETH0") (class "Default")
      (node (ref "R191") (pin "1") (pinfunction "1_1") (pintype "passive"))
      (node (ref "U41") (pin "4") (pinfunction "TRXP1_4") (pintype "passive"))
    )
    (net (code "22") (name "/MDI2_N_ETH0") (class "Default")
      (node (ref "R194") (pin "1") (pinfunction "1_1") (pintype "passive"))
      (node (ref "U41") (pin "7") (pinfunction "TRXN2_7") (pintype "passive"))
    )
    (net (code "23") (name "/MDI2_P_ETH0") (class "Default")
      (node (ref "R193") (pin "1") (pinfunction "1_1") (pintype "passive"))
      (node (ref "U41") (pin "6") (pinfunction "TRXP2_6") (pintype "passive"))
    )
    (net (code "24") (name "/MDI3_N_ETH0") (class "Default")
      (node (ref "R198") (pin "1") (pinfunction "1_1") (pintype "passive"))
      (node (ref "U41") (pin "10") (pinfunction "TRXN3_10") (pintype "passive"))
    )
    (net (code "25") (name "/MDI3_P_ETH0") (class "Default")
      (node (ref "R196") (pin "1") (pinfunction "1_1") (pintype "passive"))
      (node (ref "U41") (pin "9") (pinfunction "TRXP3_9") (pintype "passive"))
    )
    (net (code "26") (name "/XTAL_I_0") (class "Default")
      (node (ref "C164") (pin "2") (pinfunction "2_2") (pintype "passive"))
      (node (ref "U41") (pin "36") (pinfunction "XTAL_I_36") (pintype "passive"))
      (node (ref "Y3") (pin "3") (pinfunction "3_3") (pintype "passive"))
    )
    (net (code "27") (name "/XTAL_O_0") (class "Default")
      (node (ref "C163") (pin "2") (pinfunction "2_2") (pintype "passive"))
      (node (ref "U41") (pin "37") (pinfunction "XTAL_O_37") (pintype "passive"))
      (node (ref "Y3") (pin "1") (pinfunction "1_1") (pintype "passive"))
    )
    (net (code "28") (name "1A6{slash}ETH0_TXD0{slash}3V3") (class "Default")
      (node (ref "U41") (pin "18") (pinfunction "TXD0_18") (pintype "passive"))
    )
    (net (code "29") (name "1B4{slash}ETH0_RXD2{slash}3V3") (class "Default")
      (node (ref "R205") (pin "1") (pinfunction "1_1") (pintype "passive"))
    )
    (net (code "30") (name "1B6{slash}ETH0_TXD1{slash}3V3") (class "Default")
      (node (ref "U41") (pin "17") (pinfunction "TXD1_17") (pintype "passive"))
    )
    (net (code "31") (name "1C4{slash}ETH0_RXD3{slash}3V3") (class "Default")
      (node (ref "R206") (pin "1") (pinfunction "1_1") (pintype "passive"))
    )
    (net (code "32") (name "1C6{slash}ETH0_TXCTL{slash}3V3") (class "Default")
      (node (ref "U41") (pin "19") (pinfunction "TX_CTL_19") (pintype "passive"))
    )
    (net (code "33") (name "1D6{slash}ETH0_RXD0{slash}3V3") (class "Default")
      (node (ref "R203") (pin "1") (pinfunction "1_1") (pintype "passive"))
    )
    (net (code "34") (name "A5{slash}ETH0_TXD2{slash}3V3") (class "Default")
      (node (ref "U41") (pin "16") (pinfunction "TXD2_16") (pintype "passive"))
    )
    (net (code "35") (name "A7{slash}ETH0_RXD1{slash}3V3") (class "Default")
      (node (ref "R204") (pin "1") (pinfunction "1_1") (pintype "passive"))
    )
    (net (code "36") (name "A10{slash}ETH0_RXCTL{slash}3V3") (class "Default")
      (node (ref "R202") (pin "1") (pinfunction "1_1") (pintype "passive"))
    )
    (net (code "37") (name "B5{slash}ETH0_TXD3{slash}3V3") (class "Default")
      (node (ref "U41") (pin "15") (pinfunction "TXD3_15") (pintype "passive"))
    )
    (net (code "38") (name "B7{slash}ETH0_RXCLK{slash}3V3") (class "Default")
      (node (ref "R201") (pin "1") (pinfunction "1_1") (pintype "passive"))
    )
    (net (code "39") (name "B8{slash}ETH0_TXCLK{slash}3V3") (class "Default")
      (node (ref "U41") (pin "20") (pinfunction "TX_CLK_20") (pintype "passive"))
    )
    (net (code "40") (name "B9{slash}ETH0_MDC{slash}3V3") (class "Default")
      (node (ref "U41") (pin "13") (pinfunction "MDC_13") (pintype "passive"))
    )
    (net (code "41") (name "B10{slash}ETH0_MDIO{slash}3V3") (class "Default")
      (node (ref "R208") (pin "2") (pinfunction "2_2") (pintype "passive"))
      (node (ref "U41") (pin "14") (pinfunction "MDIO_14") (pintype "passive"))
    )
    (net (code "42") (name "EGND1") (class "Default")
      (node (ref "C167") (pin "1") (pinfunction "1_1") (pintype "passive"))
      (node (ref "C168") (pin "1") (pinfunction "1_1") (pintype "passive"))
      (node (ref "CON8") (pin "10") (pinfunction "GND_10") (pintype "passive"))
      (node (ref "CON8") (pin "17") (pinfunction "SHELL_GND_17") (pintype "power_in"))
      (node (ref "CON8") (pin "18") (pinfunction "SHELL_GND_18") (pintype "power_in"))
      (node (ref "D38") (pin "1") (pinfunction "ANODE1_1") (pintype "passive"))
      (node (ref "D39") (pin "1") (pinfunction "ANODE1_1") (pintype "passive"))
      (node (ref "U39") (pin "3") (pinfunction "GND_3") (pintype "power_in"))
      (node (ref "U39") (pin "8") (pinfunction "GND_8") (pintype "power_in"))
      (node (ref "U40") (pin "3") (pinfunction "GND_3") (pintype "power_in"))
      (node (ref "U40") (pin "8") (pinfunction "GND_8") (pintype "power_in"))
    )
    (net (code "43") (name "ETH0_1V1_AVDDL") (class "Default")
      (node (ref "C172") (pin "1") (pinfunction "1_1") (pintype "passive"))
      (node (ref "C173") (pin "1") (pinfunction "1_1") (pintype "passive"))
      (node (ref "C174") (pin "1") (pinfunction "1_1") (pintype "passive"))
      (node (ref "R230") (pin "2") (pinfunction "2_2") (pintype "passive"))
      (node (ref "U41") (pin "3") (pinfunction "AVDDL_3") (pintype "power_in"))
      (node (ref "U41") (pin "38") (pinfunction "AVDDL_38") (pintype "power_in"))
      (node (ref "U41") (pin "8") (pinfunction "AVDDL_8") (pintype "power_in"))
    )
    (net (code "44") (name "ETH0_1V1_DVDDL") (class "Default")
      (node (ref "C171") (pin "1") (pinfunction "1_1") (pintype "passive"))
      (node (ref "R231") (pin "2") (pinfunction "2_2") (pintype "passive"))
      (node (ref "U41") (pin "21") (pinfunction "DVDDL_21") (pintype "power_in"))
    )
    (net (code "45") (name "ETH0_1V1_ETH0L") (class "Default")
      (node (ref "C165") (pin "1") (pinfunction "1_1") (pintype "passive"))
      (node (ref "C166") (pin "1") (pinfunction "1_1") (pintype "passive"))
      (node (ref "L14") (pin "2") (pinfunction "2_2") (pintype "passive"))
      (node (ref "R230") (pin "1") (pinfunction "1_1") (pintype "passive"))
      (node (ref "R231") (pin "1") (pinfunction "1_1") (pintype "passive"))
    )
    (net (code "46") (name "ETH0_3V3_AVDD33") (class "Default")
      (node (ref "C175") (pin "1") (pinfunction "1_1") (pintype "passive"))
      (node (ref "C176") (pin "1") (pinfunction "1_1") (pintype "passive"))
      (node (ref "R229") (pin "2") (pinfunction "2_2") (pintype "passive"))
      (node (ref "U41") (pin "11") (pinfunction "AVDD33_11") (pintype "power_in"))
      (node (ref "U41") (pin "40") (pinfunction "AVDD33_40") (pintype "power_in"))
    )
    (net (code "47") (name "ETH0_3V3_DVDDRG") (class "Default")
      (node (ref "C180") (pin "1") (pinfunction "1_1") (pintype "passive"))
      (node (ref "C181") (pin "1") (pinfunction "1_1") (pintype "passive"))
      (node (ref "R208") (pin "1") (pinfunction "1_1") (pintype "passive"))
      (node (ref "R209") (pin "2") (pinfunction "2_2") (pintype "passive"))
      (node (ref "R210") (pin "2") (pinfunction "2_2") (pintype "passive"))
      (node (ref "R211") (pin "2") (pinfunction "2_2") (pintype "passive"))
      (node (ref "R212") (pin "2") (pinfunction "2_2") (pintype "passive"))
      (node (ref "R213") (pin "2") (pinfunction "2_2") (pintype "passive"))
      (node (ref "R214") (pin "2") (pinfunction "2_2") (pintype "passive"))
      (node (ref "R218") (pin "2") (pinfunction "2_2") (pintype "passive"))
      (node (ref "U41") (pin "28") (pinfunction "DVDD_RGMII_28") (pintype "power_in"))
    )
    (net (code "48") (name "ETH0_3V3_REG") (class "Default")
      (node (ref "C177") (pin "1") (pinfunction "1_1") (pintype "passive"))
      (node (ref "C178") (pin "1") (pinfunction "1_1") (pintype "passive"))
      (node (ref "C179") (pin "1") (pinfunction "1_1") (pintype "passive"))
      (node (ref "D40") (pin "1") (pinfunction "Cathode_1") (pintype "passive"))
      (node (ref "R195") (pin "2") (pinfunction "2_2") (pintype "passive"))
      (node (ref "R207") (pin "2") (pinfunction "2_2") (pintype "passive"))
      (node (ref "R215") (pin "2") (pinfunction "2_2") (pintype "passive"))
      (node (ref "R216") (pin "2") (pinfunction "2_2") (pintype "passive"))
      (node (ref "R217") (pin "2") (pinfunction "2_2") (pintype "passive"))
      (node (ref "R228") (pin "2") (pinfunction "2_2") (pintype "passive"))
      (node (ref "U41") (pin "29") (pinfunction "DVDD33_29") (pintype "power_in"))
    )
    (net (code "49") (name "GND") (class "Default")
      (node (ref "C162") (pin "1") (pinfunction "1_1") (pintype "passive"))
      (node (ref "C163") (pin "1") (pinfunction "1_1") (pintype "passive"))
      (node (ref "C164") (pin "1") (pinfunction "1_1") (pintype "passive"))
      (node (ref "C165") (pin "2") (pinfunction "2_2") (pintype "passive"))
      (node (ref "C166") (pin "2") (pinfunction "2_2") (pintype "passive"))
      (node (ref "C169") (pin "2") (pinfunction "2_2") (pintype "passive"))
      (node (ref "C170") (pin "2") (pinfunction "2_2") (pintype "passive"))
      (node (ref "C171") (pin "2") (pinfunction "2_2") (pintype "passive"))
      (node (ref "C172") (pin "2") (pinfunction "2_2") (pintype "passive"))
      (node (ref "C173") (pin "2") (pinfunction "2_2") (pintype "passive"))
      (node (ref "C174") (pin "2") (pinfunction "2_2") (pintype "passive"))
      (node (ref "C175") (pin "2") (pinfunction "2_2") (pintype "passive"))
      (node (ref "C176") (pin "2") (pinfunction "2_2") (pintype "passive"))
      (node (ref "C177") (pin "2") (pinfunction "2_2") (pintype "passive"))
      (node (ref "C178") (pin "2") (pinfunction "2_2") (pintype "passive"))
      (node (ref "C179") (pin "2") (pinfunction "2_2") (pintype "passive"))
      (node (ref "C180") (pin "2") (pinfunction "2_2") (pintype "passive"))
      (node (ref "C181") (pin "2") (pinfunction "2_2") (pintype "passive"))
      (node (ref "C182") (pin "2") (pinfunction "2_2") (pintype "passive"))
      (node (ref "C183") (pin "2") (pinfunction "2_2") (pintype "passive"))
      (node (ref "FB10") (pin "2") (pinfunction "2_2") (pintype "passive"))
      (node (ref "R197") (pin "2") (pinfunction "2_2") (pintype "passive"))
      (node (ref "R219") (pin "1") (pinfunction "1_1") (pintype "passive"))
      (node (ref "R220") (pin "1") (pinfunction "1_1") (pintype "passive"))
      (node (ref "R221") (pin "1") (pinfunction "1_1") (pintype "passive"))
      (node (ref "R222") (pin "1") (pinfunction "1_1") (pintype "passive"))
      (node (ref "R223") (pin "1") (pinfunction "1_1") (pintype "passive"))
      (node (ref "R224") (pin "1") (pinfunction "1_1") (pintype "passive"))
      (node (ref "R225") (pin "1") (pinfunction "1_1") (pintype "passive"))
      (node (ref "R226") (pin "1") (pinfunction "1_1") (pintype "passive"))
      (node (ref "R227") (pin "1") (pinfunction "1_1") (pintype "passive"))
      (node (ref "U41") (pin "41") (pinfunction "EPAD_41") (pintype "power_in"))
      (node (ref "Y3") (pin "2") (pinfunction "2_2") (pintype "passive"))
      (node (ref "Y3") (pin "4") (pinfunction "4_4") (pintype "passive"))
    )
    (net (code "50") (name "Net-(CON8-A_GRN)") (class "Default")
      (node (ref "C167") (pin "2") (pinfunction "2_2") (pintype "passive"))
      (node (ref "CON8") (pin "11") (pinfunction "A_GRN_11") (pintype "passive"))
      (node (ref "D38") (pin "2") (pinfunction "CATHODE2_2") (pintype "passive"))
      (node (ref "R199") (pin "2") (pinfunction "2_2") (pintype "passive"))
    )
    (net (code "51") (name "Net-(CON8-A_YLW)") (class "Default")
      (node (ref "CON8") (pin "12") (pinfunction "C_GRN_12") (pintype "passive"))
      (node (ref "CON8") (pin "13") (pinfunction "A_YLW_13") (pintype "passive"))
      (node (ref "FB10") (pin "1") (pinfunction "1_1") (pintype "passive"))
    )
    (net (code "52") (name "Net-(CON8-C_YLW)") (class "Default")
      (node (ref "C168") (pin "2") (pinfunction "2_2") (pintype "passive"))
      (node (ref "CON8") (pin "14") (pinfunction "C_YLW_14") (pintype "passive"))
      (node (ref "D39") (pin "2") (pinfunction "CATHODE2_2") (pintype "passive"))
      (node (ref "R200") (pin "2") (pinfunction "2_2") (pintype "passive"))
    )
    (net (code "53") (name "Net-(CON8-VCC)") (class "Default")
      (node (ref "C162") (pin "2") (pinfunction "2_2") (pintype "passive"))
      (node (ref "CON8") (pin "1") (pinfunction "VCC_1") (pintype "passive"))
    )
    (net (code "54") (name "Net-(TP12-TP)") (class "Default")
      (node (ref "TP12") (pin "1") (pinfunction "TP_1") (pintype "passive"))
      (node (ref "U41") (pin "35") (pinfunction "CLKOUT_35") (pintype "passive"))
    )
    (net (code "55") (name "Net-(U41-INT_N{slash}PME_N)") (class "Default")
      (node (ref "R195") (pin "1") (pinfunction "1_1") (pintype "passive"))
      (node (ref "U41") (pin "31") (pinfunction "INT_N/PME_N_31") (pintype "passive"))
    )
    (net (code "56") (name "Net-(U41-RBIAS)") (class "Default")
      (node (ref "R197") (pin "1") (pinfunction "1_1") (pintype "passive"))
      (node (ref "U41") (pin "39") (pinfunction "RBIAS_39") (pintype "passive"))
    )
    (net (code "57") (name "Net-(U41-REG_O{slash}LDO_O{slash}NC)") (class "Default")
      (node (ref "L14") (pin "1") (pinfunction "1_1") (pintype "passive"))
      (node (ref "U41") (pin "30") (pinfunction "REG_O/LDO_O/NC_30") (pintype "power_in"))
    )
    (net (code "58") (name "VDD_3V3_ETH0") (class "Default")
      (node (ref "C182") (pin "1") (pinfunction "1_1") (pintype "passive"))
      (node (ref "C183") (pin "1") (pinfunction "1_1") (pintype "passive"))
      (node (ref "FB11") (pin "2") (pinfunction "2_2") (pintype "passive"))
      (node (ref "R218") (pin "1") (pinfunction "1_1") (pintype "passive"))
      (node (ref "R228") (pin "1") (pinfunction "1_1") (pintype "passive"))
      (node (ref "R229") (pin "1") (pinfunction "1_1") (pintype "passive"))
    )
    (net (code "59") (name "VDD_3V3_MAIN") (class "Default")
      (node (ref "FB11") (pin "1") (pinfunction "1_1") (pintype "passive"))
    )
    (net (code "60") (name "XL9555_P00{slash}RGMII0_RST{slash}3V3") (class "Default")
      (node (ref "C170") (pin "1") (pinfunction "1_1") (pintype "passive"))
      (node (ref "D40") (pin "2") (pinfunction "Anode_2") (pintype "passive"))
      (node (ref "R207") (pin "1") (pinfunction "1_1") (pintype "passive"))
      (node (ref "U41") (pin "12") (pinfunction "RESET_N_12") (pintype "passive"))
    )
    (net (code "61") (name "unconnected-(CON8-MH1-Pad15)") (class "Default")
      (node (ref "CON8") (pin "15") (pinfunction "MH1_15") (pintype "passive+no_connect"))
    )
    (net (code "62") (name "unconnected-(CON8-MH2-Pad16)") (class "Default")
      (node (ref "CON8") (pin "16") (pinfunction "MH2_16") (pintype "passive+no_connect"))
    )
  )
)
